# Screen.net
KiCad netlist of a schematic drawn in EAGLE
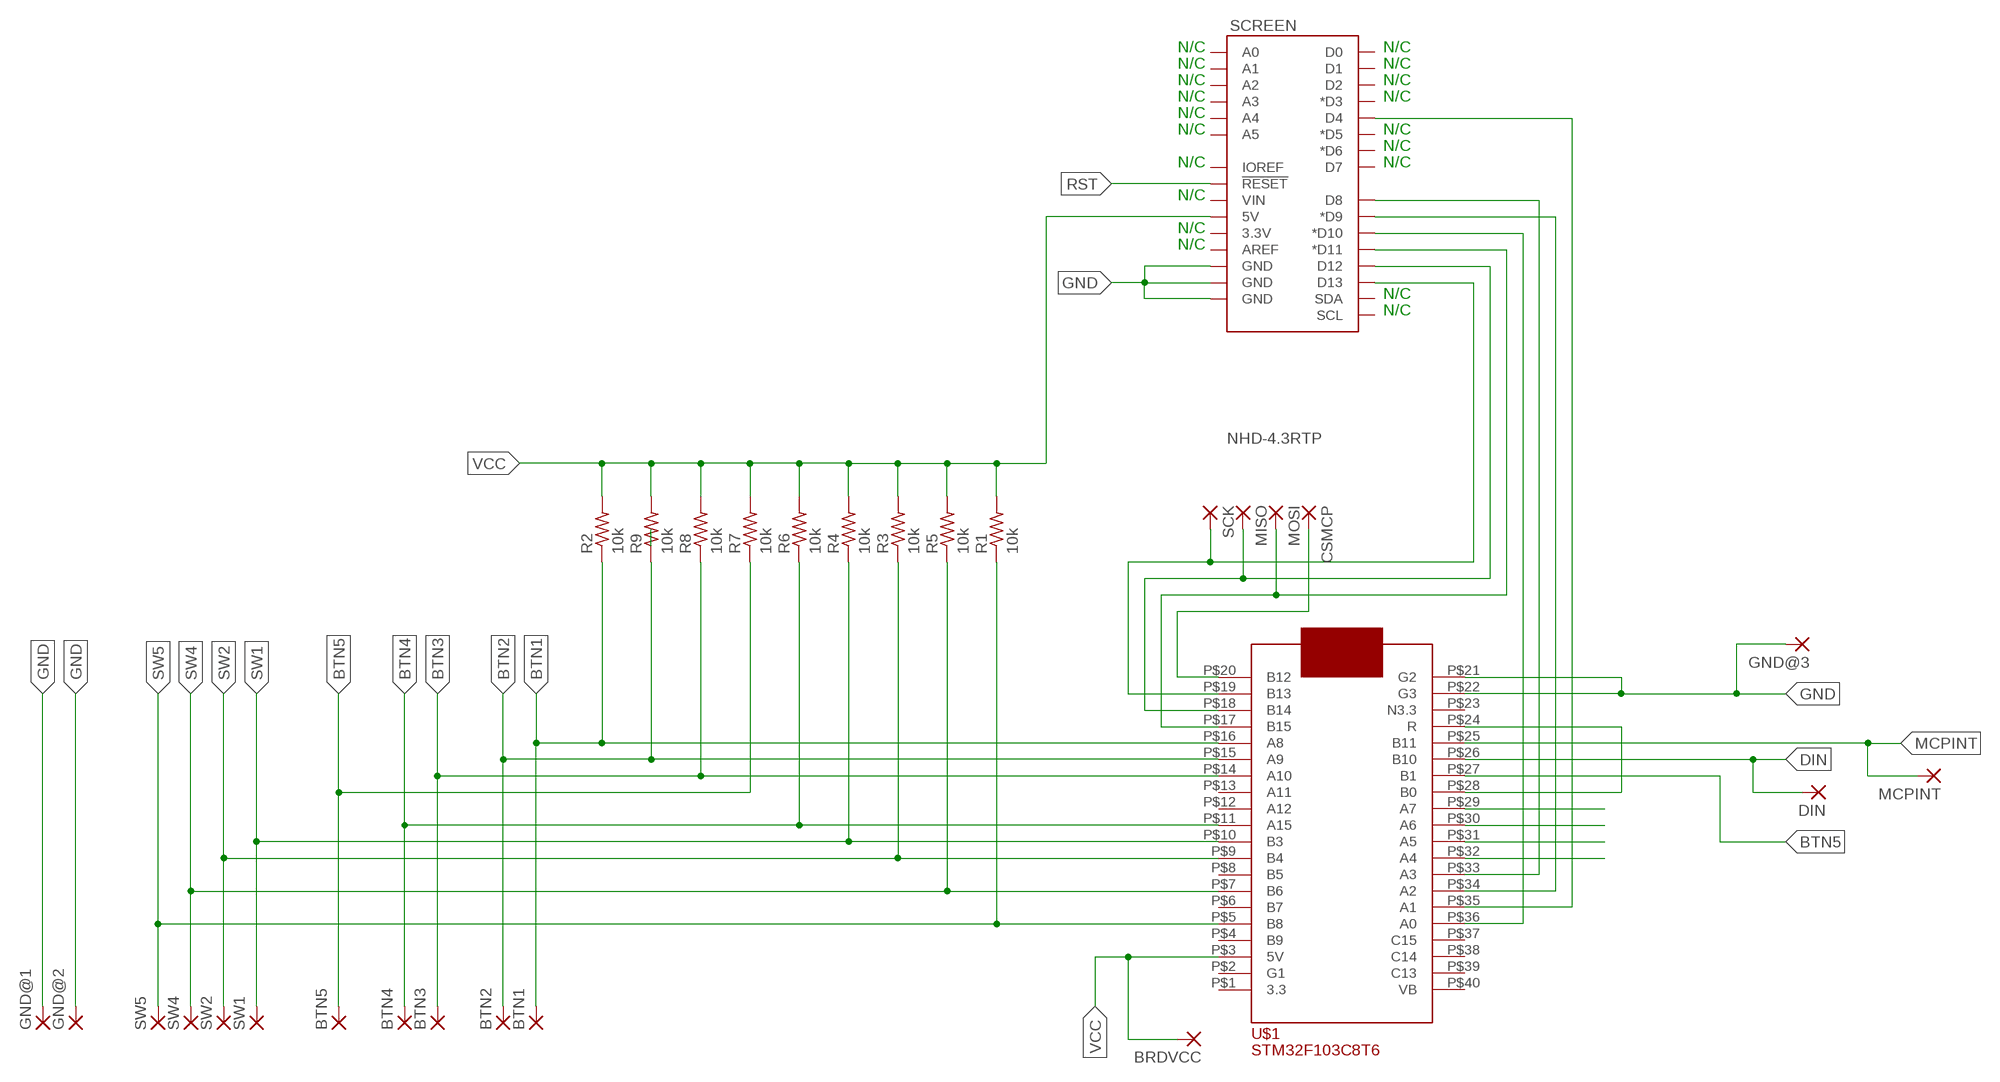
[diagram p0: schematic, sheet 1]

(export (version "E")
  (design (tool "Eeschema 10.0.6"))
  (components
    (comp (ref "BRDVCC")
      (value "SMD5")
      (footprint "eagle-import:SMD2,54-5,08")
      (libsource (lib "eagle-import") (part "SMD5"))
    )
    (comp (ref "BTN1")
      (value "SMD5")
      (footprint "eagle-import:SMD2,54-5,08")
      (libsource (lib "eagle-import") (part "SMD5"))
    )
    (comp (ref "BTN2")
      (value "SMD5")
      (footprint "eagle-import:SMD2,54-5,08")
      (libsource (lib "eagle-import") (part "SMD5"))
    )
    (comp (ref "BTN3")
      (value "SMD5")
      (footprint "eagle-import:SMD2,54-5,08")
      (libsource (lib "eagle-import") (part "SMD5"))
    )
    (comp (ref "BTN4")
      (value "SMD5")
      (footprint "eagle-import:SMD2,54-5,08")
      (libsource (lib "eagle-import") (part "SMD5"))
    )
    (comp (ref "BTN5")
      (value "SMD5")
      (footprint "eagle-import:SMD2,54-5,08")
      (libsource (lib "eagle-import") (part "SMD5"))
    )
    (comp (ref "CSMCP")
      (value "SMD5")
      (footprint "eagle-import:SMD2,54-5,08")
      (libsource (lib "eagle-import") (part "SMD5"))
    )
    (comp (ref "DIN")
      (value "SMD5")
      (footprint "eagle-import:SMD2,54-5,08")
      (libsource (lib "eagle-import") (part "SMD5"))
    )
    (comp (ref "GND@1")
      (value "SMD5")
      (footprint "eagle-import:SMD2,54-5,08")
      (libsource (lib "eagle-import") (part "SMD5"))
    )
    (comp (ref "GND@2")
      (value "SMD5")
      (footprint "eagle-import:SMD2,54-5,08")
      (libsource (lib "eagle-import") (part "SMD5"))
    )
    (comp (ref "GND@3")
      (value "SMD5")
      (footprint "eagle-import:SMD2,54-5,08")
      (libsource (lib "eagle-import") (part "SMD5"))
    )
    (comp (ref "MCPINT")
      (value "SMD5")
      (footprint "eagle-import:SMD2,54-5,08")
      (libsource (lib "eagle-import") (part "SMD5"))
    )
    (comp (ref "MISO")
      (value "SMD5")
      (footprint "eagle-import:SMD2,54-5,08")
      (libsource (lib "eagle-import") (part "SMD5"))
    )
    (comp (ref "MOSI")
      (value "SMD5")
      (footprint "eagle-import:SMD2,54-5,08")
      (libsource (lib "eagle-import") (part "SMD5"))
    )
    (comp (ref "R1")
      (value "10k")
      (footprint "eagle-import:0207_10")
      (libsource (lib "eagle-import") (part "0207/10"))
    )
    (comp (ref "R2")
      (value "10k")
      (footprint "eagle-import:0207_10")
      (libsource (lib "eagle-import") (part "0207/10"))
    )
    (comp (ref "R3")
      (value "10k")
      (footprint "eagle-import:0207_10")
      (libsource (lib "eagle-import") (part "0207/10"))
    )
    (comp (ref "R4")
      (value "10k")
      (footprint "eagle-import:0207_10")
      (libsource (lib "eagle-import") (part "0207/10"))
    )
    (comp (ref "R5")
      (value "10k")
      (footprint "eagle-import:0207_10")
      (libsource (lib "eagle-import") (part "0207/10"))
    )
    (comp (ref "R6")
      (value "10k")
      (footprint "eagle-import:0207_10")
      (libsource (lib "eagle-import") (part "0207/10"))
    )
    (comp (ref "R7")
      (value "10k")
      (footprint "eagle-import:0207_10")
      (libsource (lib "eagle-import") (part "0207/10"))
    )
    (comp (ref "R8")
      (value "10k")
      (footprint "eagle-import:0207_10")
      (libsource (lib "eagle-import") (part "0207/10"))
    )
    (comp (ref "R9")
      (value "10k")
      (footprint "eagle-import:0207_10")
      (libsource (lib "eagle-import") (part "0207/10"))
    )
    (comp (ref "SCK")
      (value "SMD5")
      (footprint "eagle-import:SMD2,54-5,08")
      (libsource (lib "eagle-import") (part "SMD5"))
    )
    (comp (ref "SCREEN")
      (value "NHD-4.3RTP")
      (footprint "eagle-import:NHD-4.3RTP")
      (libsource (lib "eagle-import") (part "NHD-4.3RTP"))
    )
    (comp (ref "SW1")
      (value "SMD5")
      (footprint "eagle-import:SMD2,54-5,08")
      (libsource (lib "eagle-import") (part "SMD5"))
    )
    (comp (ref "SW2")
      (value "SMD5")
      (footprint "eagle-import:SMD2,54-5,08")
      (libsource (lib "eagle-import") (part "SMD5"))
    )
    (comp (ref "SW4")
      (value "SMD5")
      (footprint "eagle-import:SMD2,54-5,08")
      (libsource (lib "eagle-import") (part "SMD5"))
    )
    (comp (ref "SW5")
      (value "SMD5")
      (footprint "eagle-import:SMD2,54-5,08")
      (libsource (lib "eagle-import") (part "SMD5"))
    )
    (comp (ref "U$1")
      (value "STM32F103C8T6DIP40")
      (footprint "eagle-import:STM32")
      (libsource (lib "eagle-import") (part "STM32F103C8T6DIP40"))
    )
  )
  (nets
    (net (code "1") (name "BTN1") (class "Default")
      (node (ref "BTN1") (pin "1") (pinfunction "P_1") (pintype "passive"))
      (node (ref "R2") (pin "1") (pinfunction "1_1") (pintype "passive"))
      (node (ref "U$1") (pin "P$16") (pinfunction "A8_P$16") (pintype "bidirectional"))
    )
    (net (code "2") (name "BTN2") (class "Default")
      (node (ref "BTN2") (pin "1") (pinfunction "P_1") (pintype "passive"))
      (node (ref "R9") (pin "1") (pinfunction "1_1") (pintype "passive"))
      (node (ref "U$1") (pin "P$15") (pinfunction "A9_P$15") (pintype "bidirectional"))
    )
    (net (code "3") (name "BTN3") (class "Default")
      (node (ref "BTN3") (pin "1") (pinfunction "P_1") (pintype "passive"))
      (node (ref "R8") (pin "1") (pinfunction "1_1") (pintype "passive"))
      (node (ref "U$1") (pin "P$14") (pinfunction "A10_P$14") (pintype "bidirectional"))
    )
    (net (code "4") (name "BTN4") (class "Default")
      (node (ref "BTN4") (pin "1") (pinfunction "P_1") (pintype "passive"))
      (node (ref "R6") (pin "1") (pinfunction "1_1") (pintype "passive"))
      (node (ref "U$1") (pin "P$11") (pinfunction "A15_P$11") (pintype "bidirectional"))
    )
    (net (code "5") (name "BTN5") (class "Default")
      (node (ref "BTN5") (pin "1") (pinfunction "P_1") (pintype "passive"))
      (node (ref "R7") (pin "1") (pinfunction "1_1") (pintype "passive"))
      (node (ref "U$1") (pin "P$27") (pinfunction "B1_P$27") (pintype "bidirectional"))
    )
    (net (code "6") (name "DIN") (class "Default")
      (node (ref "DIN") (pin "1") (pinfunction "P_1") (pintype "passive"))
      (node (ref "U$1") (pin "P$26") (pinfunction "B10_P$26") (pintype "bidirectional"))
    )
    (net (code "7") (name "GND") (class "Default")
      (node (ref "GND@1") (pin "1") (pinfunction "P_1") (pintype "passive"))
      (node (ref "GND@2") (pin "1") (pinfunction "P_1") (pintype "passive"))
      (node (ref "GND@3") (pin "1") (pinfunction "P_1") (pintype "passive"))
      (node (ref "SCREEN") (pin "GND@1") (pinfunction "GND_GND@1") (pintype "bidirectional"))
      (node (ref "SCREEN") (pin "GND@2") (pinfunction "GND_GND@2") (pintype "bidirectional"))
      (node (ref "SCREEN") (pin "GND@3") (pinfunction "GND_GND@3") (pintype "bidirectional"))
      (node (ref "U$1") (pin "P$21") (pinfunction "G2_P$21") (pintype "bidirectional"))
      (node (ref "U$1") (pin "P$22") (pinfunction "G3_P$22") (pintype "bidirectional"))
    )
    (net (code "8") (name "MCPINT") (class "Default")
      (node (ref "MCPINT") (pin "1") (pinfunction "P_1") (pintype "passive"))
      (node (ref "U$1") (pin "P$25") (pinfunction "B11_P$25") (pintype "bidirectional"))
    )
    (net (code "9") (name "Net-(CSMCP-P)") (class "Default")
      (node (ref "CSMCP") (pin "1") (pinfunction "P_1") (pintype "passive"))
      (node (ref "U$1") (pin "P$20") (pinfunction "B12_P$20") (pintype "bidirectional"))
    )
    (net (code "10") (name "Net-(MISO-P)") (class "Default")
      (node (ref "MISO") (pin "1") (pinfunction "P_1") (pintype "passive"))
      (node (ref "SCREEN") (pin "D12") (pinfunction "D12_D12") (pintype "bidirectional"))
      (node (ref "U$1") (pin "P$18") (pinfunction "B14_P$18") (pintype "bidirectional"))
    )
    (net (code "11") (name "Net-(MOSI-P)") (class "Default")
      (node (ref "MOSI") (pin "1") (pinfunction "P_1") (pintype "passive"))
      (node (ref "SCREEN") (pin "D11") (pinfunction "*D11_D11") (pintype "bidirectional"))
      (node (ref "U$1") (pin "P$17") (pinfunction "B15_P$17") (pintype "bidirectional"))
    )
    (net (code "12") (name "Net-(SCK-P)") (class "Default")
      (node (ref "SCK") (pin "1") (pinfunction "P_1") (pintype "passive"))
      (node (ref "SCREEN") (pin "D13") (pinfunction "D13_D13") (pintype "bidirectional"))
      (node (ref "U$1") (pin "P$19") (pinfunction "B13_P$19") (pintype "bidirectional"))
    )
    (net (code "13") (name "Net-(SCREEN-*D9)") (class "Default")
      (node (ref "SCREEN") (pin "D9") (pinfunction "*D9_D9") (pintype "bidirectional"))
      (node (ref "U$1") (pin "P$34") (pinfunction "A2_P$34") (pintype "bidirectional"))
    )
    (net (code "14") (name "Net-(SCREEN-*D10)") (class "Default")
      (node (ref "SCREEN") (pin "D10") (pinfunction "*D10_D10") (pintype "bidirectional"))
      (node (ref "U$1") (pin "P$36") (pinfunction "A0_P$36") (pintype "bidirectional"))
    )
    (net (code "15") (name "Net-(U$1-A1)") (class "Default")
      (node (ref "SCREEN") (pin "D4") (pinfunction "D4_D4") (pintype "bidirectional"))
      (node (ref "U$1") (pin "P$35") (pinfunction "A1_P$35") (pintype "bidirectional"))
    )
    (net (code "16") (name "Net-(U$1-A3)") (class "Default")
      (node (ref "SCREEN") (pin "D8") (pinfunction "D8_D8") (pintype "bidirectional"))
      (node (ref "U$1") (pin "P$33") (pinfunction "A3_P$33") (pintype "bidirectional"))
    )
    (net (code "17") (name "Net-(U$1-B0)") (class "Default")
      (node (ref "U$1") (pin "P$24") (pinfunction "R_P$24") (pintype "bidirectional"))
      (node (ref "U$1") (pin "P$28") (pinfunction "B0_P$28") (pintype "bidirectional"))
    )
    (net (code "18") (name "RST") (class "Default")
      (node (ref "SCREEN") (pin "RESET@1") (pinfunction "~{RESET}_RESET@1") (pintype "bidirectional"))
    )
    (net (code "19") (name "SW1") (class "Default")
      (node (ref "R4") (pin "1") (pinfunction "1_1") (pintype "passive"))
      (node (ref "SW1") (pin "1") (pinfunction "P_1") (pintype "passive"))
      (node (ref "U$1") (pin "P$10") (pinfunction "B3_P$10") (pintype "bidirectional"))
    )
    (net (code "20") (name "SW2") (class "Default")
      (node (ref "R3") (pin "1") (pinfunction "1_1") (pintype "passive"))
      (node (ref "SW2") (pin "1") (pinfunction "P_1") (pintype "passive"))
      (node (ref "U$1") (pin "P$9") (pinfunction "B4_P$9") (pintype "bidirectional"))
    )
    (net (code "21") (name "SW4") (class "Default")
      (node (ref "R5") (pin "1") (pinfunction "1_1") (pintype "passive"))
      (node (ref "SW4") (pin "1") (pinfunction "P_1") (pintype "passive"))
      (node (ref "U$1") (pin "P$7") (pinfunction "B6_P$7") (pintype "bidirectional"))
    )
    (net (code "22") (name "SW5") (class "Default")
      (node (ref "R1") (pin "1") (pinfunction "1_1") (pintype "passive"))
      (node (ref "SW5") (pin "1") (pinfunction "P_1") (pintype "passive"))
      (node (ref "U$1") (pin "P$5") (pinfunction "B8_P$5") (pintype "bidirectional"))
    )
    (net (code "23") (name "VCC") (class "Default")
      (node (ref "BRDVCC") (pin "1") (pinfunction "P_1") (pintype "passive"))
      (node (ref "R1") (pin "2") (pinfunction "2_2") (pintype "passive"))
      (node (ref "R2") (pin "2") (pinfunction "2_2") (pintype "passive"))
      (node (ref "R3") (pin "2") (pinfunction "2_2") (pintype "passive"))
      (node (ref "R4") (pin "2") (pinfunction "2_2") (pintype "passive"))
      (node (ref "R5") (pin "2") (pinfunction "2_2") (pintype "passive"))
      (node (ref "R6") (pin "2") (pinfunction "2_2") (pintype "passive"))
      (node (ref "R7") (pin "2") (pinfunction "2_2") (pintype "passive"))
      (node (ref "R8") (pin "2") (pinfunction "2_2") (pintype "passive"))
      (node (ref "R9") (pin "2") (pinfunction "2_2") (pintype "passive"))
      (node (ref "SCREEN") (pin "5V") (pinfunction "5V_5V") (pintype "bidirectional"))
      (node (ref "U$1") (pin "P$3") (pinfunction "5V_P$3") (pintype "bidirectional"))
    )
    (net (code "24") (name "unconnected-(SCREEN-*D3-PadD3)") (class "Default")
      (node (ref "SCREEN") (pin "D3") (pinfunction "*D3_D3") (pintype "bidirectional"))
    )
    (net (code "25") (name "unconnected-(SCREEN-*D5-PadD5)") (class "Default")
      (node (ref "SCREEN") (pin "D5") (pinfunction "*D5_D5") (pintype "bidirectional"))
    )
    (net (code "26") (name "unconnected-(SCREEN-*D6-PadD6)") (class "Default")
      (node (ref "SCREEN") (pin "D6") (pinfunction "*D6_D6") (pintype "bidirectional"))
    )
    (net (code "27") (name "unconnected-(SCREEN-Pad3.3V)") (class "Default")
      (node (ref "SCREEN") (pin "3.3V") (pinfunction "3.3V_3.3V") (pintype "bidirectional"))
    )
    (net (code "28") (name "unconnected-(SCREEN-PadA0)") (class "Default")
      (node (ref "SCREEN") (pin "A0") (pinfunction "A0_A0") (pintype "bidirectional"))
    )
    (net (code "29") (name "unconnected-(SCREEN-PadA1)") (class "Default")
      (node (ref "SCREEN") (pin "A1") (pinfunction "A1_A1") (pintype "bidirectional"))
    )
    (net (code "30") (name "unconnected-(SCREEN-PadA2)") (class "Default")
      (node (ref "SCREEN") (pin "A2") (pinfunction "A2_A2") (pintype "bidirectional"))
    )
    (net (code "31") (name "unconnected-(SCREEN-PadA3)") (class "Default")
      (node (ref "SCREEN") (pin "A3") (pinfunction "A3_A3") (pintype "bidirectional"))
    )
    (net (code "32") (name "unconnected-(SCREEN-PadA4)") (class "Default")
      (node (ref "SCREEN") (pin "A4") (pinfunction "A4_A4") (pintype "bidirectional"))
    )
    (net (code "33") (name "unconnected-(SCREEN-PadA5)") (class "Default")
      (node (ref "SCREEN") (pin "A5") (pinfunction "A5_A5") (pintype "bidirectional"))
    )
    (net (code "34") (name "unconnected-(SCREEN-PadAREF)") (class "Default")
      (node (ref "SCREEN") (pin "AREF") (pinfunction "AREF_AREF") (pintype "bidirectional"))
    )
    (net (code "35") (name "unconnected-(SCREEN-PadD0)") (class "Default")
      (node (ref "SCREEN") (pin "D0") (pinfunction "D0_D0") (pintype "bidirectional"))
    )
    (net (code "36") (name "unconnected-(SCREEN-PadD1)") (class "Default")
      (node (ref "SCREEN") (pin "D1") (pinfunction "D1_D1") (pintype "bidirectional"))
    )
    (net (code "37") (name "unconnected-(SCREEN-PadD2)") (class "Default")
      (node (ref "SCREEN") (pin "D2") (pinfunction "D2_D2") (pintype "bidirectional"))
    )
    (net (code "38") (name "unconnected-(SCREEN-PadD7)") (class "Default")
      (node (ref "SCREEN") (pin "D7") (pinfunction "D7_D7") (pintype "bidirectional"))
    )
    (net (code "39") (name "unconnected-(SCREEN-PadIOREF)") (class "Default")
      (node (ref "SCREEN") (pin "IOREF") (pinfunction "IOREF_IOREF") (pintype "bidirectional"))
    )
    (net (code "40") (name "unconnected-(SCREEN-PadSCL)") (class "Default")
      (node (ref "SCREEN") (pin "SCL") (pinfunction "SCL_SCL") (pintype "bidirectional"))
    )
    (net (code "41") (name "unconnected-(SCREEN-PadSDA)") (class "Default")
      (node (ref "SCREEN") (pin "SDA") (pinfunction "SDA_SDA") (pintype "bidirectional"))
    )
    (net (code "42") (name "unconnected-(SCREEN-PadVIN)") (class "Default")
      (node (ref "SCREEN") (pin "VIN") (pinfunction "VIN_VIN") (pintype "bidirectional"))
    )
    (net (code "43") (name "unconnected-(U$1-3.3-PadP$1)") (class "Default")
      (node (ref "U$1") (pin "P$1") (pinfunction "3.3_P$1") (pintype "bidirectional"))
    )
    (net (code "44") (name "unconnected-(U$1-A4-PadP$32)") (class "Default")
      (node (ref "U$1") (pin "P$32") (pinfunction "A4_P$32") (pintype "bidirectional"))
    )
    (net (code "45") (name "unconnected-(U$1-A5-PadP$31)") (class "Default")
      (node (ref "U$1") (pin "P$31") (pinfunction "A5_P$31") (pintype "bidirectional"))
    )
    (net (code "46") (name "unconnected-(U$1-A6-PadP$30)") (class "Default")
      (node (ref "U$1") (pin "P$30") (pinfunction "A6_P$30") (pintype "bidirectional"))
    )
    (net (code "47") (name "unconnected-(U$1-A7-PadP$29)") (class "Default")
      (node (ref "U$1") (pin "P$29") (pinfunction "A7_P$29") (pintype "bidirectional"))
    )
    (net (code "48") (name "unconnected-(U$1-A11-PadP$13)") (class "Default")
      (node (ref "U$1") (pin "P$13") (pinfunction "A11_P$13") (pintype "bidirectional"))
    )
    (net (code "49") (name "unconnected-(U$1-A12-PadP$12)") (class "Default")
      (node (ref "U$1") (pin "P$12") (pinfunction "A12_P$12") (pintype "bidirectional"))
    )
    (net (code "50") (name "unconnected-(U$1-B5-PadP$8)") (class "Default")
      (node (ref "U$1") (pin "P$8") (pinfunction "B5_P$8") (pintype "bidirectional"))
    )
    (net (code "51") (name "unconnected-(U$1-B7-PadP$6)") (class "Default")
      (node (ref "U$1") (pin "P$6") (pinfunction "B7_P$6") (pintype "bidirectional"))
    )
    (net (code "52") (name "unconnected-(U$1-B9-PadP$4)") (class "Default")
      (node (ref "U$1") (pin "P$4") (pinfunction "B9_P$4") (pintype "bidirectional"))
    )
    (net (code "53") (name "unconnected-(U$1-C13-PadP$39)") (class "Default")
      (node (ref "U$1") (pin "P$39") (pinfunction "C13_P$39") (pintype "bidirectional"))
    )
    (net (code "54") (name "unconnected-(U$1-C14-PadP$38)") (class "Default")
      (node (ref "U$1") (pin "P$38") (pinfunction "C14_P$38") (pintype "bidirectional"))
    )
    (net (code "55") (name "unconnected-(U$1-C15-PadP$37)") (class "Default")
      (node (ref "U$1") (pin "P$37") (pinfunction "C15_P$37") (pintype "bidirectional"))
    )
    (net (code "56") (name "unconnected-(U$1-G1-PadP$2)") (class "Default")
      (node (ref "U$1") (pin "P$2") (pinfunction "G1_P$2") (pintype "bidirectional"))
    )
    (net (code "57") (name "unconnected-(U$1-N3.3-PadP$23)") (class "Default")
      (node (ref "U$1") (pin "P$23") (pinfunction "N3.3_P$23") (pintype "bidirectional"))
    )
    (net (code "58") (name "unconnected-(U$1-VB-PadP$40)") (class "Default")
      (node (ref "U$1") (pin "P$40") (pinfunction "VB_P$40") (pintype "bidirectional"))
    )
  )
)
